# CFWatch_EasyEDA.net
KiCad netlist of a schematic drawn in EasyEDA Pro
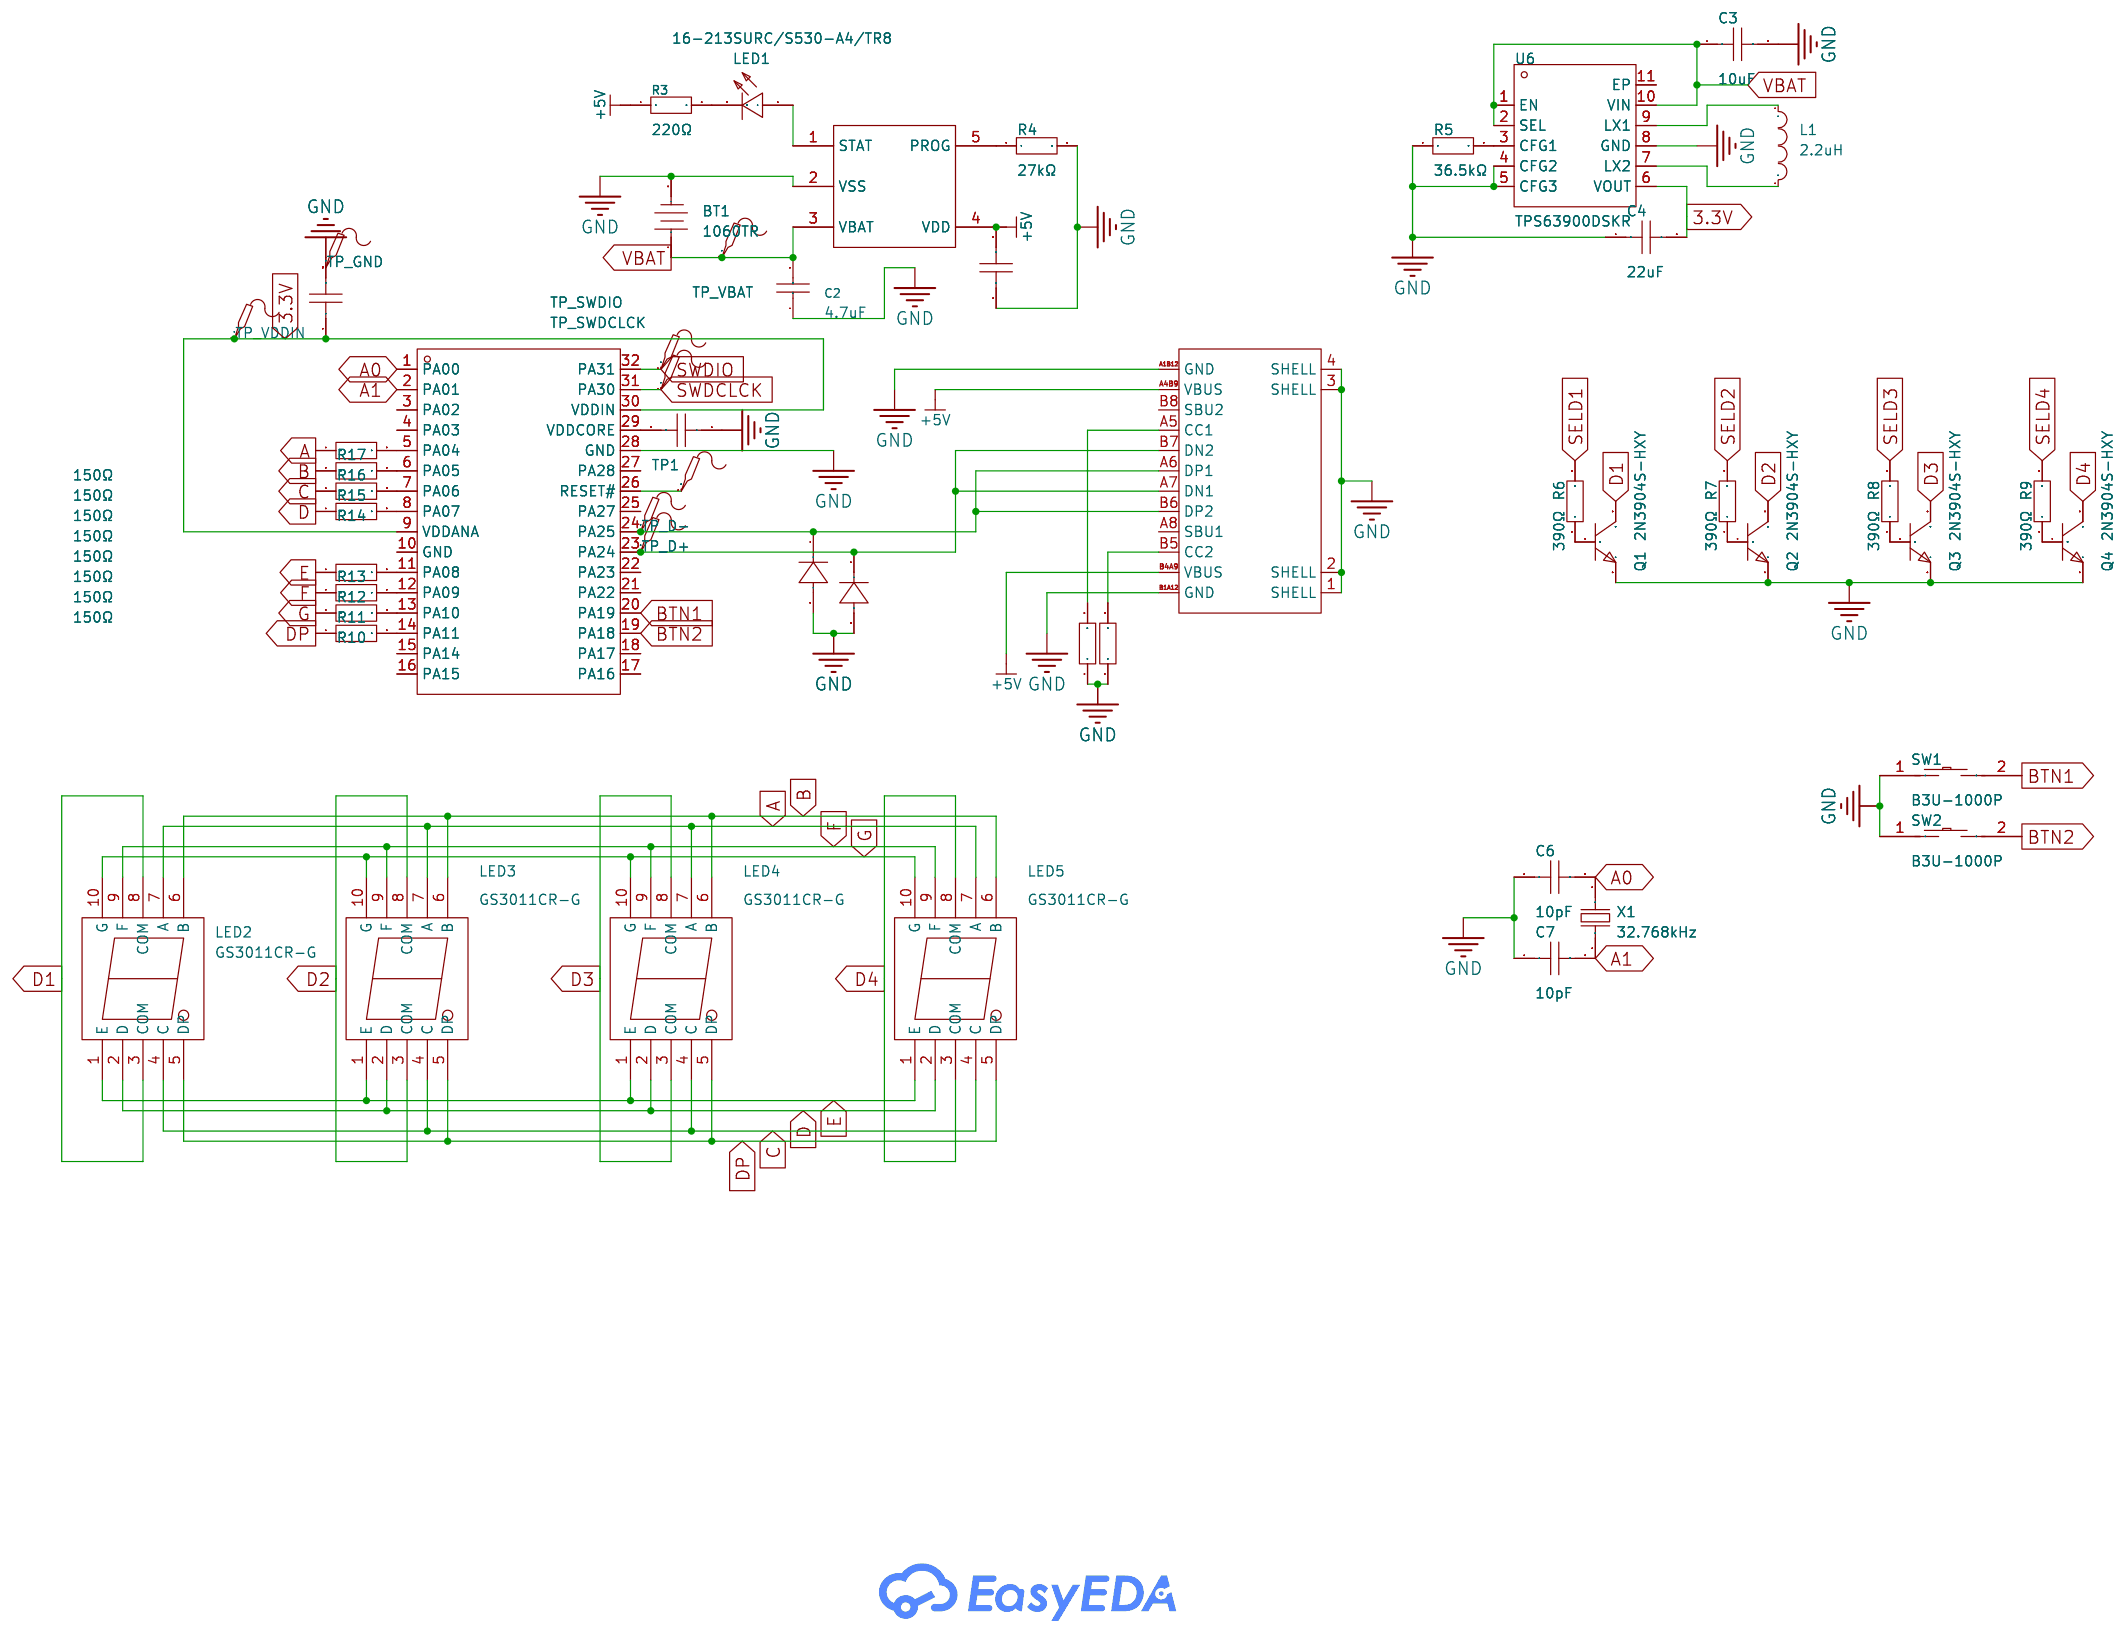
[diagram p0: schematic sheet]

(export (version "E")
  (design (tool "Eeschema 10.0.6"))
  (components
    (comp (ref "BT1")
      (value "1060TR")
      (footprint "easyedapro:BAT-SMD_1060TR")
      (fields (field (name "Manufacturer") "Keystone"))
      (libsource (lib "easyedapro") (part "1060TR"))
    )
    (comp (ref "C1")
      (value "1uF")
      (footprint "easyedapro:C0402")
      (fields
        (field (name "Manufacturer Part") "CL05A105KA5NQNC")
        (field (name "Manufacturer") "SAMSUNG(三星)")
      )
      (libsource (lib "easyedapro") (part "CL05A105KA5NQNC"))
    )
    (comp (ref "C2")
      (value "4.7uF")
      (footprint "easyedapro:C0402")
      (fields
        (field (name "Manufacturer Part") "CL05A475MP5NRNC")
        (field (name "Manufacturer") "SAMSUNG(三星)")
      )
      (libsource (lib "easyedapro") (part "CL05A475MP5NRNC"))
    )
    (comp (ref "C3")
      (value "10uF")
      (footprint "easyedapro:C0402")
      (description "Capacitance:10uF Tolerance:±20% Tolerance:±20% Voltage Rating:6.3V Temperature Coefficient:X5R")
      (fields
        (field (name "Manufacturer Part") "CGA0402X5R106M6R3GT")
        (field (name "Manufacturer") "HRE(芯声)")
      )
      (libsource (lib "easyedapro") (part "CGA0402X5R106M6R3GT"))
    )
    (comp (ref "C4")
      (value "22uF")
      (footprint "easyedapro:C0402")
      (description "Capacitance:22uF Tolerance:±20% Tolerance:±20% Voltage Rating:6.3V Temperature Coefficient:X5R")
      (fields
        (field (name "Manufacturer Part") "GRM155R60J226ME11D")
        (field (name "Manufacturer") "muRata(村田)")
      )
      (libsource (lib "easyedapro") (part "GRM155R60J226ME11D"))
    )
    (comp (ref "C5")
      (value "1uF")
      (footprint "easyedapro:C0402")
      (fields
        (field (name "Manufacturer Part") "CL05A105KA5NQNC")
        (field (name "Manufacturer") "SAMSUNG(三星)")
      )
      (libsource (lib "easyedapro") (part "CL05A105KA5NQNC"))
    )
    (comp (ref "C6")
      (value "10pF")
      (footprint "easyedapro:C0402")
      (fields
        (field (name "Manufacturer Part") "CL05C100JB5NNNC")
        (field (name "Manufacturer") "SAMSUNG(三星)")
      )
      (libsource (lib "easyedapro") (part "CL05C100JB5NNNC"))
    )
    (comp (ref "C7")
      (value "10pF")
      (footprint "easyedapro:C0402")
      (fields
        (field (name "Manufacturer Part") "CL05C100JB5NNNC")
        (field (name "Manufacturer") "SAMSUNG(三星)")
      )
      (libsource (lib "easyedapro") (part "CL05C100JB5NNNC"))
    )
    (comp (ref "C8")
      (value "1uF")
      (footprint "easyedapro:C0402")
      (fields
        (field (name "Manufacturer Part") "CL05A105KA5NQNC")
        (field (name "Manufacturer") "SAMSUNG(三星)")
      )
      (libsource (lib "easyedapro") (part "CL05A105KA5NQNC"))
    )
    (comp (ref "L1")
      (value "2.2uH")
      (footprint "easyedapro:L0805")
      (fields (field (name "Manufacturer Part") "CMI201209U2R2KT") (field (name "Manufacturer") "FH(风华)"))
      (libsource (lib "easyedapro") (part "CMI201209U2R2KT"))
    )
    (comp (ref "LED1")
      (value "16-213SURC/S530-A4/TR8")
      (footprint "easyedapro:LED0402-R-RD")
      (fields (field (name "Manufacturer") "EVERLIGHT(亿光)"))
      (libsource (lib "easyedapro") (part "16-213SURC/S530-A4/TR8"))
    )
    (comp (ref "LED2")
      (value "GS3011CR-G")
      (footprint "easyedapro:LED-SEG-SMD_10P-L12.0-W7.3-P1.50-BL")
      (fields (field (name "Manufacturer") "Guangcai Display(光彩显示)"))
      (libsource (lib "easyedapro") (part "GS3011CR-G"))
    )
    (comp (ref "LED3")
      (value "GS3011CR-G")
      (footprint "easyedapro:LED-SEG-SMD_10P-L12.0-W7.3-P1.50-BL")
      (fields (field (name "Manufacturer") "Guangcai Display(光彩显示)"))
      (libsource (lib "easyedapro") (part "GS3011CR-G"))
    )
    (comp (ref "LED4")
      (value "GS3011CR-G")
      (footprint "easyedapro:LED-SEG-SMD_10P-L12.0-W7.3-P1.50-BL")
      (fields (field (name "Manufacturer") "Guangcai Display(光彩显示)"))
      (libsource (lib "easyedapro") (part "GS3011CR-G"))
    )
    (comp (ref "LED5")
      (value "GS3011CR-G")
      (footprint "easyedapro:LED-SEG-SMD_10P-L12.0-W7.3-P1.50-BL")
      (fields (field (name "Manufacturer") "Guangcai Display(光彩显示)"))
      (libsource (lib "easyedapro") (part "GS3011CR-G"))
    )
    (comp (ref "Q1")
      (value "2N3904S-HXY")
      (footprint "easyedapro:SOT-23-3_L3.0-W1.7-P0.95-LS2.9-BR")
      (fields (field (name "Manufacturer") "HXY MOSFET(华轩阳电子)"))
      (libsource (lib "easyedapro") (part "2N3904S-HXY"))
    )
    (comp (ref "Q2")
      (value "2N3904S-HXY")
      (footprint "easyedapro:SOT-23-3_L3.0-W1.7-P0.95-LS2.9-BR")
      (fields (field (name "Manufacturer") "HXY MOSFET(华轩阳电子)"))
      (libsource (lib "easyedapro") (part "2N3904S-HXY"))
    )
    (comp (ref "Q3")
      (value "2N3904S-HXY")
      (footprint "easyedapro:SOT-23-3_L3.0-W1.7-P0.95-LS2.9-BR")
      (fields (field (name "Manufacturer") "HXY MOSFET(华轩阳电子)"))
      (libsource (lib "easyedapro") (part "2N3904S-HXY"))
    )
    (comp (ref "Q4")
      (value "2N3904S-HXY")
      (footprint "easyedapro:SOT-23-3_L3.0-W1.7-P0.95-LS2.9-BR")
      (fields (field (name "Manufacturer") "HXY MOSFET(华轩阳电子)"))
      (libsource (lib "easyedapro") (part "2N3904S-HXY"))
    )
    (comp (ref "R1")
      (value "5.1kΩ")
      (footprint "easyedapro:R0402")
      (fields
        (field (name "Manufacturer Part") "0402WGF5101TCE")
        (field (name "Manufacturer") "UNI-ROYAL(厚声)")
      )
      (libsource (lib "easyedapro") (part "0402WGF5101TCE"))
    )
    (comp (ref "R2")
      (value "5.1kΩ")
      (footprint "easyedapro:R0402")
      (fields
        (field (name "Manufacturer Part") "0402WGF5101TCE")
        (field (name "Manufacturer") "UNI-ROYAL(厚声)")
      )
      (libsource (lib "easyedapro") (part "0402WGF5101TCE"))
    )
    (comp (ref "R3")
      (value "220Ω")
      (footprint "easyedapro:R0402")
      (fields
        (field (name "Manufacturer Part") "0402WGF2200TCE")
        (field (name "Manufacturer") "UNI-ROYAL(厚声)")
      )
      (libsource (lib "easyedapro") (part "0402WGF2200TCE"))
    )
    (comp (ref "R4")
      (value "27kΩ")
      (footprint "easyedapro:R0402")
      (fields
        (field (name "Manufacturer Part") "0402WGF2702TCE")
        (field (name "Manufacturer") "UNI-ROYAL(厚声)")
      )
      (libsource (lib "easyedapro") (part "0402WGF2702TCE"))
    )
    (comp (ref "R5")
      (value "36.5kΩ")
      (footprint "easyedapro:R0402")
      (fields (field (name "Manufacturer Part") "RC0402FR-0736K5L") (field (name "Manufacturer") "YAGEO(国巨)"))
      (libsource (lib "easyedapro") (part "RC0402FR-0736K5L"))
    )
    (comp (ref "R6")
      (value "390Ω")
      (footprint "easyedapro:R0402")
      (fields (field (name "Manufacturer Part") "RC0402FR-07390RL") (field (name "Manufacturer") "YAGEO(国巨)"))
      (libsource (lib "easyedapro") (part "RC0402FR-07390RL"))
    )
    (comp (ref "R7")
      (value "390Ω")
      (footprint "easyedapro:R0402")
      (fields (field (name "Manufacturer Part") "RC0402FR-07390RL") (field (name "Manufacturer") "YAGEO(国巨)"))
      (libsource (lib "easyedapro") (part "RC0402FR-07390RL"))
    )
    (comp (ref "R8")
      (value "390Ω")
      (footprint "easyedapro:R0402")
      (fields (field (name "Manufacturer Part") "RC0402FR-07390RL") (field (name "Manufacturer") "YAGEO(国巨)"))
      (libsource (lib "easyedapro") (part "RC0402FR-07390RL"))
    )
    (comp (ref "R9")
      (value "390Ω")
      (footprint "easyedapro:R0402")
      (fields (field (name "Manufacturer Part") "RC0402FR-07390RL") (field (name "Manufacturer") "YAGEO(国巨)"))
      (libsource (lib "easyedapro") (part "RC0402FR-07390RL"))
    )
    (comp (ref "R10")
      (value "150Ω")
      (footprint "easyedapro:R0402")
      (fields (field (name "Manufacturer Part") "RC0402FR-07150RL") (field (name "Manufacturer") "YAGEO(国巨)"))
      (libsource (lib "easyedapro") (part "RC0402FR-07150RL"))
    )
    (comp (ref "R11")
      (value "150Ω")
      (footprint "easyedapro:R0402")
      (fields (field (name "Manufacturer Part") "RC0402FR-07150RL") (field (name "Manufacturer") "YAGEO(国巨)"))
      (libsource (lib "easyedapro") (part "RC0402FR-07150RL"))
    )
    (comp (ref "R12")
      (value "150Ω")
      (footprint "easyedapro:R0402")
      (fields (field (name "Manufacturer Part") "RC0402FR-07150RL") (field (name "Manufacturer") "YAGEO(国巨)"))
      (libsource (lib "easyedapro") (part "RC0402FR-07150RL"))
    )
    (comp (ref "R13")
      (value "150Ω")
      (footprint "easyedapro:R0402")
      (fields (field (name "Manufacturer Part") "RC0402FR-07150RL") (field (name "Manufacturer") "YAGEO(国巨)"))
      (libsource (lib "easyedapro") (part "RC0402FR-07150RL"))
    )
    (comp (ref "R14")
      (value "150Ω")
      (footprint "easyedapro:R0402")
      (fields (field (name "Manufacturer Part") "RC0402FR-07150RL") (field (name "Manufacturer") "YAGEO(国巨)"))
      (libsource (lib "easyedapro") (part "RC0402FR-07150RL"))
    )
    (comp (ref "R15")
      (value "150Ω")
      (footprint "easyedapro:R0402")
      (fields (field (name "Manufacturer Part") "RC0402FR-07150RL") (field (name "Manufacturer") "YAGEO(国巨)"))
      (libsource (lib "easyedapro") (part "RC0402FR-07150RL"))
    )
    (comp (ref "R16")
      (value "150Ω")
      (footprint "easyedapro:R0402")
      (fields (field (name "Manufacturer Part") "RC0402FR-07150RL") (field (name "Manufacturer") "YAGEO(国巨)"))
      (libsource (lib "easyedapro") (part "RC0402FR-07150RL"))
    )
    (comp (ref "R17")
      (value "150Ω")
      (footprint "easyedapro:R0402")
      (fields (field (name "Manufacturer Part") "RC0402FR-07150RL") (field (name "Manufacturer") "YAGEO(国巨)"))
      (libsource (lib "easyedapro") (part "RC0402FR-07150RL"))
    )
    (comp (ref "SW1")
      (value "B3U-1000P")
      (footprint "easyedapro:KEY-SMD_B3U-1000PM")
      (fields (field (name "Manufacturer") "OMRON(欧姆龙)"))
      (libsource (lib "easyedapro") (part "B3U-1000P"))
    )
    (comp (ref "SW2")
      (value "B3U-1000P")
      (footprint "easyedapro:KEY-SMD_B3U-1000PM")
      (fields (field (name "Manufacturer") "OMRON(欧姆龙)"))
      (libsource (lib "easyedapro") (part "B3U-1000P"))
    )
    (comp (ref "TP1")
      (value "~")
      (footprint "easyedapro:Test-Point-0.5mm")
      (description "Test Point 测试点")
      (libsource (lib "easyedapro") (part "Test-Point"))
    )
    (comp (ref "TP_D+")
      (value "~")
      (footprint "easyedapro:Test-Point-0.5mm")
      (description "Test Point 测试点")
      (libsource (lib "easyedapro") (part "Test-Point"))
    )
    (comp (ref "TP_D-")
      (value "~")
      (footprint "easyedapro:Test-Point-0.5mm")
      (description "Test Point 测试点")
      (libsource (lib "easyedapro") (part "Test-Point"))
    )
    (comp (ref "TP_GND")
      (value "~")
      (footprint "easyedapro:Test-Point-0.5mm")
      (description "Test Point 测试点")
      (libsource (lib "easyedapro") (part "Test-Point"))
    )
    (comp (ref "TP_SWDCLCK")
      (value "~")
      (footprint "easyedapro:Test-Point-0.5mm")
      (description "Test Point 测试点")
      (libsource (lib "easyedapro") (part "Test-Point"))
    )
    (comp (ref "TP_SWDIO")
      (value "~")
      (footprint "easyedapro:Test-Point-0.5mm")
      (description "Test Point 测试点")
      (libsource (lib "easyedapro") (part "Test-Point"))
    )
    (comp (ref "TP_VBAT")
      (value "~")
      (footprint "easyedapro:Test-Point-0.5mm")
      (description "Test Point 测试点")
      (libsource (lib "easyedapro") (part "Test-Point"))
    )
    (comp (ref "TP_VDDIN")
      (value "~")
      (footprint "easyedapro:Test-Point-0.5mm")
      (description "Test Point 测试点")
      (libsource (lib "easyedapro") (part "Test-Point"))
    )
    (comp (ref "U1")
      (value "ATSAMD21E18A-AF")
      (footprint "easyedapro:TQFP-32_L7.0-W7.0-P0.80-LS9.0-BL")
      (fields (field (name "Manufacturer") "MICROCHIP(美国微芯)"))
      (libsource (lib "easyedapro") (part "ATSAMD21E18A-AF"))
    )
    (comp (ref "U2")
      (value "GT-USB-7010ASV")
      (footprint "easyedapro:USB-C-SMD_G-SWITCH_GT-USB-7010ASV")
      (fields (field (name "Manufacturer") "G-Switch(品赞)"))
      (libsource (lib "easyedapro") (part "GT-USB-7010ASV"))
    )
    (comp (ref "U3")
      (value "1N5819WS")
      (footprint "easyedapro:SOD-323_L1.8-W1.3-LS2.5-RD")
      (fields (field (name "Manufacturer") "HXY MOSFET(华轩阳电子)"))
      (libsource (lib "easyedapro") (part "1N5819WS_C5451629"))
    )
    (comp (ref "U4")
      (value "1N5819WS")
      (footprint "easyedapro:SOD-323_L1.8-W1.3-LS2.5-RD")
      (fields (field (name "Manufacturer") "HXY MOSFET(华轩阳电子)"))
      (libsource (lib "easyedapro") (part "1N5819WS_C5451629"))
    )
    (comp (ref "U5")
      (value "MCP73831T-2ATI/OT")
      (footprint "easyedapro:SOT-23-5_L3.0-W1.7-P0.95-LS2.8-BR")
      (fields (field (name "Manufacturer") "MICROCHIP(美国微芯)"))
      (libsource (lib "easyedapro") (part "MCP73831T-2ATI/OT"))
    )
    (comp (ref "U6")
      (value "TPS63900DSKR")
      (footprint "easyedapro:WSON-10_L2.5-W2.5-W0.50-TL-EP")
      (fields (field (name "Manufacturer") "TI(德州仪器)"))
      (libsource (lib "easyedapro") (part "TPS63900DSKR"))
    )
    (comp (ref "X1")
      (value "32.768kHz")
      (footprint "easyedapro:FC-135R_L3.2-W1.5")
      (fields (field (name "Manufacturer Part") "Q13FC13500004") (field (name "Manufacturer") "EPSON(爱普生)"))
      (libsource (lib "easyedapro") (part "Q13FC1350000400"))
    )
  )
  (nets
    (net (code "1") (name "+5V") (class "Default")
      (node (ref "C1") (pin "2") (pinfunction "2_2") (pintype "unspecified"))
      (node (ref "R3") (pin "1") (pinfunction "1_1") (pintype "input"))
      (node (ref "U2") (pin "A4B9") (pinfunction "VBUS_A4B9") (pintype "unspecified"))
      (node (ref "U2") (pin "B4A9") (pinfunction "VBUS_B4A9") (pintype "unspecified"))
      (node (ref "U5") (pin "4") (pinfunction "VDD_4") (pintype "input"))
    )
    (net (code "2") (name "3.3V") (class "Default")
      (node (ref "C4") (pin "2") (pinfunction "2_2") (pintype "unspecified"))
      (node (ref "C5") (pin "1") (pinfunction "1_1") (pintype "unspecified"))
      (node (ref "TP_VDDIN") (pin "1") (pinfunction "1_1") (pintype "unspecified"))
      (node (ref "U1") (pin "30") (pinfunction "VDDIN_30") (pintype "unspecified"))
      (node (ref "U1") (pin "9") (pinfunction "VDDANA_9") (pintype "unspecified"))
      (node (ref "U6") (pin "6") (pinfunction "VOUT_6") (pintype "unspecified"))
    )
    (net (code "3") (name "A") (class "Default")
      (node (ref "LED2") (pin "7") (pinfunction "A_7") (pintype "unspecified"))
      (node (ref "LED3") (pin "7") (pinfunction "A_7") (pintype "unspecified"))
      (node (ref "LED4") (pin "7") (pinfunction "A_7") (pintype "unspecified"))
      (node (ref "LED5") (pin "7") (pinfunction "A_7") (pintype "unspecified"))
      (node (ref "R17") (pin "1") (pinfunction "1_1") (pintype "input"))
    )
    (net (code "4") (name "A0") (class "Default")
      (node (ref "C6") (pin "2") (pinfunction "2_2") (pintype "unspecified"))
      (node (ref "U1") (pin "1") (pinfunction "PA00_1") (pintype "unspecified"))
      (node (ref "X1") (pin "2") (pinfunction "2_2") (pintype "unspecified"))
    )
    (net (code "5") (name "A1") (class "Default")
      (node (ref "C7") (pin "2") (pinfunction "2_2") (pintype "unspecified"))
      (node (ref "U1") (pin "2") (pinfunction "PA01_2") (pintype "unspecified"))
      (node (ref "X1") (pin "1") (pinfunction "1_1") (pintype "unspecified"))
    )
    (net (code "6") (name "B") (class "Default")
      (node (ref "LED2") (pin "6") (pinfunction "B_6") (pintype "unspecified"))
      (node (ref "LED3") (pin "6") (pinfunction "B_6") (pintype "unspecified"))
      (node (ref "LED4") (pin "6") (pinfunction "B_6") (pintype "unspecified"))
      (node (ref "LED5") (pin "6") (pinfunction "B_6") (pintype "unspecified"))
      (node (ref "R16") (pin "1") (pinfunction "1_1") (pintype "input"))
    )
    (net (code "7") (name "BTN1") (class "Default")
      (node (ref "SW1") (pin "2") (pinfunction "2_2") (pintype "unspecified"))
      (node (ref "U1") (pin "20") (pinfunction "PA19_20") (pintype "unspecified"))
    )
    (net (code "8") (name "BTN2") (class "Default")
      (node (ref "SW2") (pin "2") (pinfunction "2_2") (pintype "unspecified"))
      (node (ref "U1") (pin "19") (pinfunction "PA18_19") (pintype "unspecified"))
    )
    (net (code "9") (name "C") (class "Default")
      (node (ref "LED2") (pin "4") (pinfunction "C_4") (pintype "unspecified"))
      (node (ref "LED3") (pin "4") (pinfunction "C_4") (pintype "unspecified"))
      (node (ref "LED4") (pin "4") (pinfunction "C_4") (pintype "unspecified"))
      (node (ref "LED5") (pin "4") (pinfunction "C_4") (pintype "unspecified"))
      (node (ref "R15") (pin "1") (pinfunction "1_1") (pintype "input"))
    )
    (net (code "10") (name "D") (class "Default")
      (node (ref "LED2") (pin "2") (pinfunction "D_2") (pintype "unspecified"))
      (node (ref "LED3") (pin "2") (pinfunction "D_2") (pintype "unspecified"))
      (node (ref "LED4") (pin "2") (pinfunction "D_2") (pintype "unspecified"))
      (node (ref "LED5") (pin "2") (pinfunction "D_2") (pintype "unspecified"))
      (node (ref "R14") (pin "1") (pinfunction "1_1") (pintype "input"))
    )
    (net (code "11") (name "D1") (class "Default")
      (node (ref "LED2") (pin "3") (pinfunction "COM_3") (pintype "unspecified"))
      (node (ref "LED2") (pin "8") (pinfunction "COM_8") (pintype "unspecified"))
      (node (ref "Q1") (pin "3") (pinfunction "C_3") (pintype "input"))
    )
    (net (code "12") (name "D2") (class "Default")
      (node (ref "LED3") (pin "3") (pinfunction "COM_3") (pintype "unspecified"))
      (node (ref "LED3") (pin "8") (pinfunction "COM_8") (pintype "unspecified"))
      (node (ref "Q2") (pin "3") (pinfunction "C_3") (pintype "input"))
    )
    (net (code "13") (name "D3") (class "Default")
      (node (ref "LED4") (pin "3") (pinfunction "COM_3") (pintype "unspecified"))
      (node (ref "LED4") (pin "8") (pinfunction "COM_8") (pintype "unspecified"))
      (node (ref "Q3") (pin "3") (pinfunction "C_3") (pintype "input"))
    )
    (net (code "14") (name "D4") (class "Default")
      (node (ref "LED5") (pin "3") (pinfunction "COM_3") (pintype "unspecified"))
      (node (ref "LED5") (pin "8") (pinfunction "COM_8") (pintype "unspecified"))
      (node (ref "Q4") (pin "3") (pinfunction "C_3") (pintype "input"))
    )
    (net (code "15") (name "DP") (class "Default")
      (node (ref "LED2") (pin "5") (pinfunction "DP_5") (pintype "unspecified"))
      (node (ref "LED3") (pin "5") (pinfunction "DP_5") (pintype "unspecified"))
      (node (ref "LED4") (pin "5") (pinfunction "DP_5") (pintype "unspecified"))
      (node (ref "LED5") (pin "5") (pinfunction "DP_5") (pintype "unspecified"))
      (node (ref "R10") (pin "1") (pinfunction "1_1") (pintype "input"))
    )
    (net (code "16") (name "E") (class "Default")
      (node (ref "LED2") (pin "1") (pinfunction "E_1") (pintype "unspecified"))
      (node (ref "LED3") (pin "1") (pinfunction "E_1") (pintype "unspecified"))
      (node (ref "LED4") (pin "1") (pinfunction "E_1") (pintype "unspecified"))
      (node (ref "LED5") (pin "1") (pinfunction "E_1") (pintype "unspecified"))
      (node (ref "R13") (pin "1") (pinfunction "1_1") (pintype "input"))
    )
    (net (code "17") (name "F") (class "Default")
      (node (ref "LED2") (pin "9") (pinfunction "F_9") (pintype "unspecified"))
      (node (ref "LED3") (pin "9") (pinfunction "F_9") (pintype "unspecified"))
      (node (ref "LED4") (pin "9") (pinfunction "F_9") (pintype "unspecified"))
      (node (ref "LED5") (pin "9") (pinfunction "F_9") (pintype "unspecified"))
      (node (ref "R12") (pin "1") (pinfunction "1_1") (pintype "input"))
    )
    (net (code "18") (name "G") (class "Default")
      (node (ref "LED2") (pin "10") (pinfunction "G_10") (pintype "unspecified"))
      (node (ref "LED3") (pin "10") (pinfunction "G_10") (pintype "unspecified"))
      (node (ref "LED4") (pin "10") (pinfunction "G_10") (pintype "unspecified"))
      (node (ref "LED5") (pin "10") (pinfunction "G_10") (pintype "unspecified"))
      (node (ref "R11") (pin "1") (pinfunction "1_1") (pintype "input"))
    )
    (net (code "19") (name "GND") (class "Default")
      (node (ref "BT1") (pin "2") (pinfunction "-_2") (pintype "unspecified"))
      (node (ref "C1") (pin "1") (pinfunction "1_1") (pintype "unspecified"))
      (node (ref "C2") (pin "1") (pinfunction "1_1") (pintype "input"))
      (node (ref "C3") (pin "2") (pinfunction "2_2") (pintype "unspecified"))
      (node (ref "C4") (pin "1") (pinfunction "1_1") (pintype "unspecified"))
      (node (ref "C5") (pin "2") (pinfunction "2_2") (pintype "unspecified"))
      (node (ref "C6") (pin "1") (pinfunction "1_1") (pintype "unspecified"))
      (node (ref "C7") (pin "1") (pinfunction "1_1") (pintype "unspecified"))
      (node (ref "C8") (pin "1") (pinfunction "1_1") (pintype "unspecified"))
      (node (ref "Q1") (pin "2") (pinfunction "E_2") (pintype "input"))
      (node (ref "Q2") (pin "2") (pinfunction "E_2") (pintype "input"))
      (node (ref "Q3") (pin "2") (pinfunction "E_2") (pintype "input"))
      (node (ref "Q4") (pin "2") (pinfunction "E_2") (pintype "input"))
      (node (ref "R1") (pin "1") (pinfunction "1_1") (pintype "input"))
      (node (ref "R2") (pin "1") (pinfunction "1_1") (pintype "input"))
      (node (ref "R4") (pin "2") (pinfunction "2_2") (pintype "input"))
      (node (ref "R5") (pin "1") (pinfunction "1_1") (pintype "input"))
      (node (ref "SW1") (pin "1") (pinfunction "1_1") (pintype "unspecified"))
      (node (ref "SW2") (pin "1") (pinfunction "1_1") (pintype "unspecified"))
      (node (ref "U1") (pin "28") (pinfunction "GND_28") (pintype "unspecified"))
      (node (ref "U2") (pin "1") (pinfunction "SHELL_1") (pintype "unspecified"))
      (node (ref "U2") (pin "2") (pinfunction "SHELL_2") (pintype "unspecified"))
      (node (ref "U2") (pin "3") (pinfunction "SHELL_3") (pintype "unspecified"))
      (node (ref "U2") (pin "4") (pinfunction "SHELL_4") (pintype "unspecified"))
      (node (ref "U2") (pin "A1B12") (pinfunction "GND_A1B12") (pintype "unspecified"))
      (node (ref "U2") (pin "B1A12") (pinfunction "GND_B1A12") (pintype "unspecified"))
      (node (ref "U3") (pin "2") (pinfunction "A_2") (pintype "unspecified"))
      (node (ref "U4") (pin "2") (pinfunction "A_2") (pintype "unspecified"))
      (node (ref "U5") (pin "2") (pinfunction "VSS_2") (pintype "input"))
      (node (ref "U6") (pin "4") (pinfunction "CFG2_4") (pintype "unspecified"))
      (node (ref "U6") (pin "5") (pinfunction "CFG3_5") (pintype "unspecified"))
      (node (ref "U6") (pin "8") (pinfunction "GND_8") (pintype "unspecified"))
    )
    (net (code "20") (name "Net-(LED1-A)") (class "Default")
      (node (ref "LED1") (pin "1") (pinfunction "A_1") (pintype "input"))
      (node (ref "U5") (pin "1") (pinfunction "STAT_1") (pintype "input"))
    )
    (net (code "21") (name "Net-(LED1-C)") (class "Default")
      (node (ref "LED1") (pin "2") (pinfunction "C_2") (pintype "input"))
      (node (ref "R3") (pin "2") (pinfunction "2_2") (pintype "input"))
    )
    (net (code "22") (name "Net-(Q1-B)") (class "Default")
      (node (ref "Q1") (pin "1") (pinfunction "B_1") (pintype "input"))
      (node (ref "R6") (pin "1") (pinfunction "1_1") (pintype "input"))
    )
    (net (code "23") (name "Net-(Q2-B)") (class "Default")
      (node (ref "Q2") (pin "1") (pinfunction "B_1") (pintype "input"))
      (node (ref "R7") (pin "1") (pinfunction "1_1") (pintype "input"))
    )
    (net (code "24") (name "Net-(Q3-B)") (class "Default")
      (node (ref "Q3") (pin "1") (pinfunction "B_1") (pintype "input"))
      (node (ref "R8") (pin "1") (pinfunction "1_1") (pintype "input"))
    )
    (net (code "25") (name "Net-(Q4-B)") (class "Default")
      (node (ref "Q4") (pin "1") (pinfunction "B_1") (pintype "input"))
      (node (ref "R9") (pin "1") (pinfunction "1_1") (pintype "input"))
    )
    (net (code "26") (name "Net-(U1-PA04)") (class "Default")
      (node (ref "R17") (pin "2") (pinfunction "2_2") (pintype "input"))
      (node (ref "U1") (pin "5") (pinfunction "PA04_5") (pintype "unspecified"))
    )
    (net (code "27") (name "Net-(U1-PA05)") (class "Default")
      (node (ref "R16") (pin "2") (pinfunction "2_2") (pintype "input"))
      (node (ref "U1") (pin "6") (pinfunction "PA05_6") (pintype "unspecified"))
    )
    (net (code "28") (name "Net-(U1-PA06)") (class "Default")
      (node (ref "R15") (pin "2") (pinfunction "2_2") (pintype "input"))
      (node (ref "U1") (pin "7") (pinfunction "PA06_7") (pintype "unspecified"))
    )
    (net (code "29") (name "Net-(U1-PA07)") (class "Default")
      (node (ref "R14") (pin "2") (pinfunction "2_2") (pintype "input"))
      (node (ref "U1") (pin "8") (pinfunction "PA07_8") (pintype "unspecified"))
    )
    (net (code "30") (name "Net-(U1-PA08)") (class "Default")
      (node (ref "R13") (pin "2") (pinfunction "2_2") (pintype "input"))
      (node (ref "U1") (pin "11") (pinfunction "PA08_11") (pintype "unspecified"))
    )
    (net (code "31") (name "Net-(U1-PA09)") (class "Default")
      (node (ref "R12") (pin "2") (pinfunction "2_2") (pintype "input"))
      (node (ref "U1") (pin "12") (pinfunction "PA09_12") (pintype "unspecified"))
    )
    (net (code "32") (name "Net-(U1-PA10)") (class "Default")
      (node (ref "R11") (pin "2") (pinfunction "2_2") (pintype "input"))
      (node (ref "U1") (pin "13") (pinfunction "PA10_13") (pintype "unspecified"))
    )
    (net (code "33") (name "Net-(U1-PA11)") (class "Default")
      (node (ref "R10") (pin "2") (pinfunction "2_2") (pintype "input"))
      (node (ref "U1") (pin "14") (pinfunction "PA11_14") (pintype "unspecified"))
    )
    (net (code "34") (name "Net-(U1-PA24)") (class "Default")
      (node (ref "TP_D+") (pin "1") (pinfunction "1_1") (pintype "unspecified"))
      (node (ref "U1") (pin "23") (pinfunction "PA24_23") (pintype "unspecified"))
      (node (ref "U2") (pin "A7") (pinfunction "DN1_A7") (pintype "unspecified"))
      (node (ref "U2") (pin "B7") (pinfunction "DN2_B7") (pintype "unspecified"))
      (node (ref "U4") (pin "1") (pinfunction "K_1") (pintype "unspecified"))
    )
    (net (code "35") (name "Net-(U1-PA25)") (class "Default")
      (node (ref "TP_D-") (pin "1") (pinfunction "1_1") (pintype "unspecified"))
      (node (ref "U1") (pin "24") (pinfunction "PA25_24") (pintype "unspecified"))
      (node (ref "U2") (pin "A6") (pinfunction "DP1_A6") (pintype "unspecified"))
      (node (ref "U2") (pin "B6") (pinfunction "DP2_B6") (pintype "unspecified"))
      (node (ref "U3") (pin "1") (pinfunction "K_1") (pintype "unspecified"))
    )
    (net (code "36") (name "Net-(U1-RESET#)") (class "Default")
      (node (ref "TP1") (pin "1") (pinfunction "1_1") (pintype "unspecified"))
      (node (ref "U1") (pin "26") (pinfunction "RESET#_26") (pintype "unspecified"))
    )
    (net (code "37") (name "Net-(U1-VDDCORE)") (class "Default")
      (node (ref "C8") (pin "2") (pinfunction "2_2") (pintype "unspecified"))
      (node (ref "U1") (pin "29") (pinfunction "VDDCORE_29") (pintype "unspecified"))
    )
    (net (code "38") (name "Net-(U2-CC1)") (class "Default")
      (node (ref "R1") (pin "2") (pinfunction "2_2") (pintype "input"))
      (node (ref "U2") (pin "A5") (pinfunction "CC1_A5") (pintype "unspecified"))
    )
    (net (code "39") (name "Net-(U2-CC2)") (class "Default")
      (node (ref "R2") (pin "2") (pinfunction "2_2") (pintype "input"))
      (node (ref "U2") (pin "B5") (pinfunction "CC2_B5") (pintype "unspecified"))
    )
    (net (code "40") (name "Net-(U5-PROG)") (class "Default")
      (node (ref "R4") (pin "1") (pinfunction "1_1") (pintype "input"))
      (node (ref "U5") (pin "5") (pinfunction "PROG_5") (pintype "input"))
    )
    (net (code "41") (name "Net-(U6-CFG1)") (class "Default")
      (node (ref "R5") (pin "2") (pinfunction "2_2") (pintype "input"))
      (node (ref "U6") (pin "3") (pinfunction "CFG1_3") (pintype "unspecified"))
    )
    (net (code "42") (name "Net-(U6-LX1)") (class "Default")
      (node (ref "L1") (pin "1") (pinfunction "1_1") (pintype "unspecified"))
      (node (ref "U6") (pin "9") (pinfunction "LX1_9") (pintype "unspecified"))
    )
    (net (code "43") (name "Net-(U6-LX2)") (class "Default")
      (node (ref "L1") (pin "2") (pinfunction "2_2") (pintype "unspecified"))
      (node (ref "U6") (pin "7") (pinfunction "LX2_7") (pintype "unspecified"))
    )
    (net (code "44") (name "SELD1") (class "Default")
      (node (ref "R6") (pin "2") (pinfunction "2_2") (pintype "input"))
    )
    (net (code "45") (name "SELD2") (class "Default")
      (node (ref "R7") (pin "2") (pinfunction "2_2") (pintype "input"))
    )
    (net (code "46") (name "SELD3") (class "Default")
      (node (ref "R8") (pin "2") (pinfunction "2_2") (pintype "input"))
    )
    (net (code "47") (name "SELD4") (class "Default")
      (node (ref "R9") (pin "2") (pinfunction "2_2") (pintype "input"))
    )
    (net (code "48") (name "SWDCLCK") (class "Default")
      (node (ref "TP_SWDCLCK") (pin "1") (pinfunction "1_1") (pintype "unspecified"))
      (node (ref "U1") (pin "31") (pinfunction "PA30_31") (pintype "unspecified"))
    )
    (net (code "49") (name "SWDIO") (class "Default")
      (node (ref "TP_SWDIO") (pin "1") (pinfunction "1_1") (pintype "unspecified"))
      (node (ref "U1") (pin "32") (pinfunction "PA31_32") (pintype "unspecified"))
    )
    (net (code "50") (name "VBAT") (class "Default")
      (node (ref "BT1") (pin "1") (pinfunction "+_1") (pintype "unspecified"))
      (node (ref "C2") (pin "2") (pinfunction "2_2") (pintype "input"))
      (node (ref "C3") (pin "1") (pinfunction "1_1") (pintype "unspecified"))
      (node (ref "TP_VBAT") (pin "1") (pinfunction "1_1") (pintype "unspecified"))
      (node (ref "U5") (pin "3") (pinfunction "VBAT_3") (pintype "input"))
      (node (ref "U6") (pin "1") (pinfunction "EN_1") (pintype "unspecified"))
      (node (ref "U6") (pin "10") (pinfunction "VIN_10") (pintype "unspecified"))
      (node (ref "U6") (pin "2") (pinfunction "SEL_2") (pintype "unspecified"))
    )
    (net (code "51") (name "unconnected-(TP_GND-Pad1)") (class "Default")
      (node (ref "TP_GND") (pin "1") (pinfunction "1_1") (pintype "unspecified"))
    )
    (net (code "52") (name "unconnected-(U1-GND-Pad10)") (class "Default")
      (node (ref "U1") (pin "10") (pinfunction "GND_10") (pintype "unspecified"))
    )
    (net (code "53") (name "unconnected-(U1-PA02-Pad3)") (class "Default")
      (node (ref "U1") (pin "3") (pinfunction "PA02_3") (pintype "unspecified"))
    )
    (net (code "54") (name "unconnected-(U1-PA03-Pad4)") (class "Default")
      (node (ref "U1") (pin "4") (pinfunction "PA03_4") (pintype "unspecified"))
    )
    (net (code "55") (name "unconnected-(U1-PA14-Pad15)") (class "Default")
      (node (ref "U1") (pin "15") (pinfunction "PA14_15") (pintype "unspecified"))
    )
    (net (code "56") (name "unconnected-(U1-PA15-Pad16)") (class "Default")
      (node (ref "U1") (pin "16") (pinfunction "PA15_16") (pintype "unspecified"))
    )
    (net (code "57") (name "unconnected-(U1-PA16-Pad17)") (class "Default")
      (node (ref "U1") (pin "17") (pinfunction "PA16_17") (pintype "unspecified"))
    )
    (net (code "58") (name "unconnected-(U1-PA17-Pad18)") (class "Default")
      (node (ref "U1") (pin "18") (pinfunction "PA17_18") (pintype "unspecified"))
    )
    (net (code "59") (name "unconnected-(U1-PA22-Pad21)") (class "Default")
      (node (ref "U1") (pin "21") (pinfunction "PA22_21") (pintype "unspecified"))
    )
    (net (code "60") (name "unconnected-(U1-PA23-Pad22)") (class "Default")
      (node (ref "U1") (pin "22") (pinfunction "PA23_22") (pintype "unspecified"))
    )
    (net (code "61") (name "unconnected-(U1-PA27-Pad25)") (class "Default")
      (node (ref "U1") (pin "25") (pinfunction "PA27_25") (pintype "unspecified"))
    )
    (net (code "62") (name "unconnected-(U1-PA28-Pad27)") (class "Default")
      (node (ref "U1") (pin "27") (pinfunction "PA28_27") (pintype "unspecified"))
    )
    (net (code "63") (name "unconnected-(U2-SBU1-PadA8)") (class "Default")
      (node (ref "U2") (pin "A8") (pinfunction "SBU1_A8") (pintype "unspecified"))
    )
    (net (code "64") (name "unconnected-(U2-SBU2-PadB8)") (class "Default")
      (node (ref "U2") (pin "B8") (pinfunction "SBU2_B8") (pintype "unspecified"))
    )
    (net (code "65") (name "unconnected-(U6-EP-Pad11)") (class "Default")
      (node (ref "U6") (pin "11") (pinfunction "EP_11") (pintype "unspecified"))
    )
  )
)
